# RFMxx-LPC812.net
KiCad netlist of a schematic drawn in EAGLE
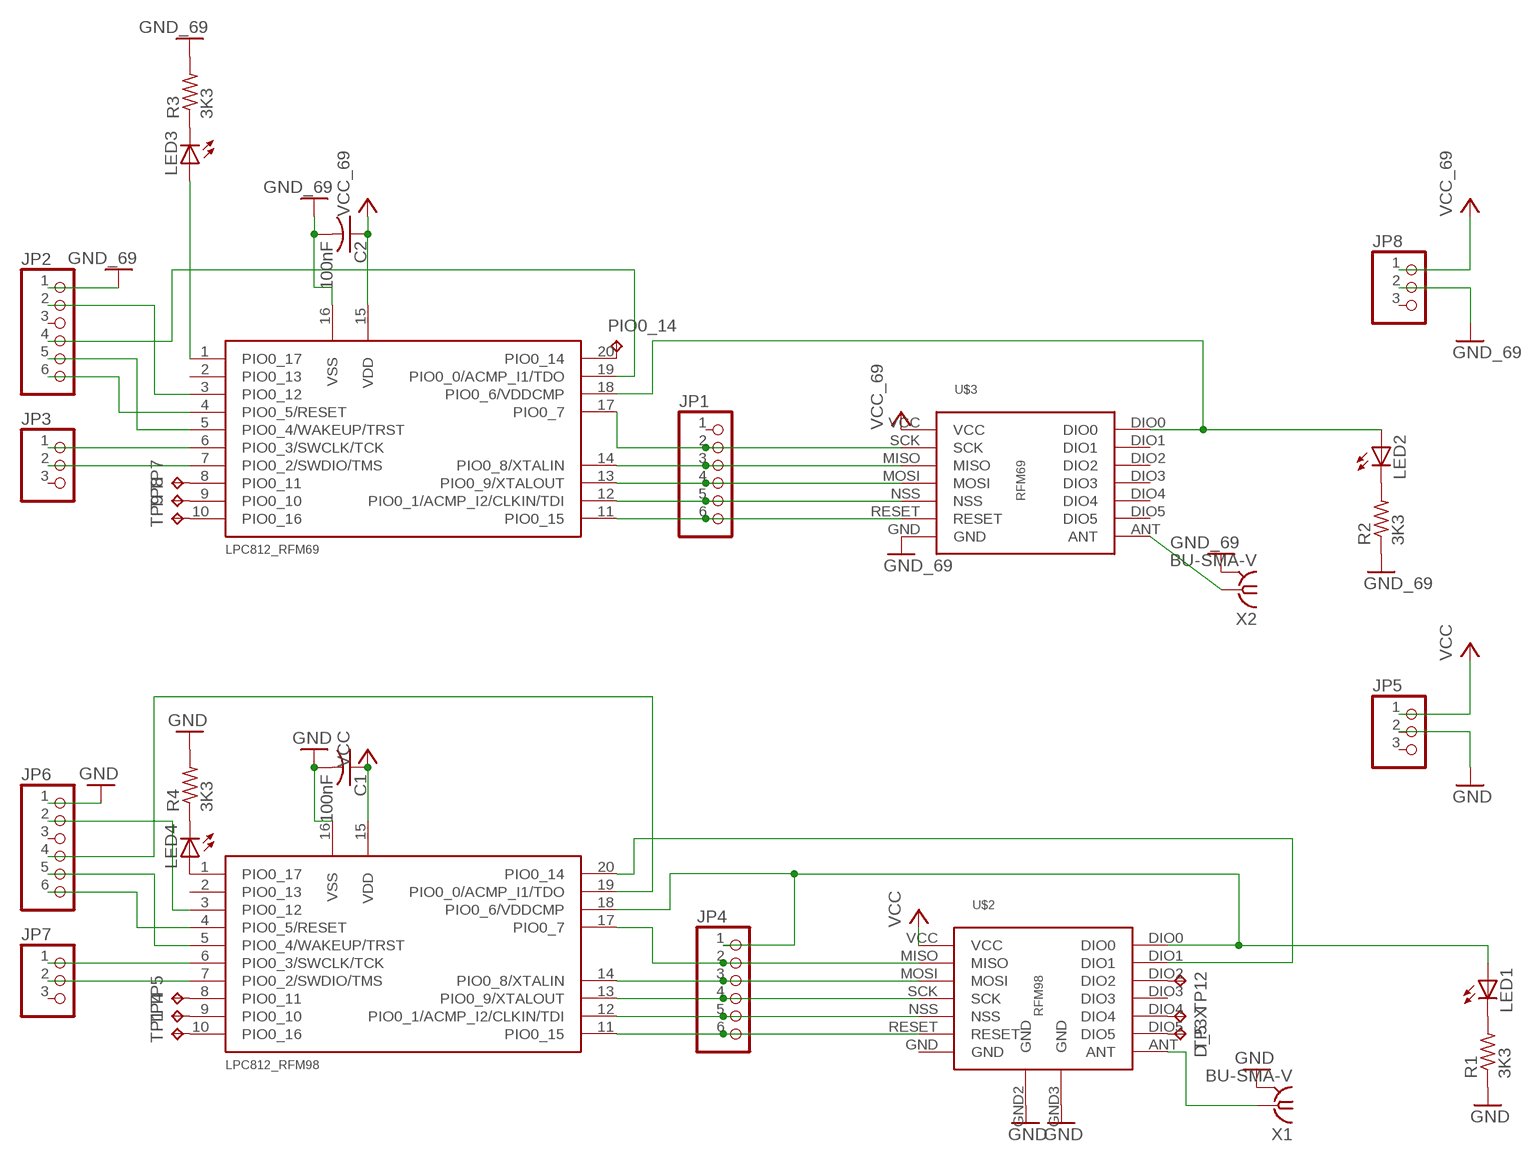
[diagram p0: schematic, sheet 1]

(export (version "E")
  (design (tool "Eeschema 10.0.6"))
  (components
    (comp (ref "C1")
      (value "100nF")
      (footprint "eagle-import:C0805")
      (libsource (lib "eagle-import") (part "C-USC0805"))
    )
    (comp (ref "C2")
      (value "100nF")
      (footprint "eagle-import:C0805")
      (libsource (lib "eagle-import") (part "C-USC0805"))
    )
    (comp (ref "D_5")
      (value "TPB1,27")
      (footprint "eagle-import:B1,27")
      (libsource (lib "eagle-import") (part "TPB1,27"))
    )
    (comp (ref "JP1")
      (value "PINHD-1X6")
      (footprint "eagle-import:1X06")
      (libsource (lib "eagle-import") (part "PINHD-1X6"))
    )
    (comp (ref "JP2")
      (value "PINHD-1X6")
      (footprint "eagle-import:1X06")
      (libsource (lib "eagle-import") (part "PINHD-1X6"))
    )
    (comp (ref "JP3")
      (value "PINHD-1X3")
      (footprint "eagle-import:1X03")
      (libsource (lib "eagle-import") (part "PINHD-1X3"))
    )
    (comp (ref "JP4")
      (value "PINHD-1X6")
      (footprint "eagle-import:1X06")
      (libsource (lib "eagle-import") (part "PINHD-1X6"))
    )
    (comp (ref "JP5")
      (value "PINHD-1X3")
      (footprint "eagle-import:1X03")
      (libsource (lib "eagle-import") (part "PINHD-1X3"))
    )
    (comp (ref "JP6")
      (value "PINHD-1X6")
      (footprint "eagle-import:1X06")
      (libsource (lib "eagle-import") (part "PINHD-1X6"))
    )
    (comp (ref "JP7")
      (value "PINHD-1X3")
      (footprint "eagle-import:1X03")
      (libsource (lib "eagle-import") (part "PINHD-1X3"))
    )
    (comp (ref "JP8")
      (value "PINHD-1X3")
      (footprint "eagle-import:1X03")
      (libsource (lib "eagle-import") (part "PINHD-1X3"))
    )
    (comp (ref "LED1")
      (value "LEDCHIP-LED0805")
      (footprint "eagle-import:CHIP-LED0805")
      (libsource (lib "eagle-import") (part "LEDCHIP-LED0805"))
    )
    (comp (ref "LED2")
      (value "LEDCHIP-LED0805")
      (footprint "eagle-import:CHIP-LED0805")
      (libsource (lib "eagle-import") (part "LEDCHIP-LED0805"))
    )
    (comp (ref "LED3")
      (value "LEDCHIP-LED0805")
      (footprint "eagle-import:CHIP-LED0805")
      (libsource (lib "eagle-import") (part "LEDCHIP-LED0805"))
    )
    (comp (ref "LED4")
      (value "LEDCHIP-LED0805")
      (footprint "eagle-import:CHIP-LED0805")
      (libsource (lib "eagle-import") (part "LEDCHIP-LED0805"))
    )
    (comp (ref "LPC812_RFM69")
      (value "LPC812M101JD20")
      (footprint "eagle-import:SOIC20")
      (libsource (lib "eagle-import") (part "LPC812M101JD20"))
    )
    (comp (ref "LPC812_RFM98")
      (value "LPC812M101JD20")
      (footprint "eagle-import:SOIC20")
      (libsource (lib "eagle-import") (part "LPC812M101JD20"))
    )
    (comp (ref "PIO0_14")
      (value "TPB1,27")
      (footprint "eagle-import:B1,27")
      (libsource (lib "eagle-import") (part "TPB1,27"))
    )
    (comp (ref "R1")
      (value "3K3")
      (footprint "eagle-import:R0805")
      (libsource (lib "eagle-import") (part "R-US_R0805"))
    )
    (comp (ref "R2")
      (value "3K3")
      (footprint "eagle-import:R0805")
      (libsource (lib "eagle-import") (part "R-US_R0805"))
    )
    (comp (ref "R3")
      (value "3K3")
      (footprint "eagle-import:R0805")
      (libsource (lib "eagle-import") (part "R-US_R0805"))
    )
    (comp (ref "R4")
      (value "3K3")
      (footprint "eagle-import:R0805")
      (libsource (lib "eagle-import") (part "R-US_R0805"))
    )
    (comp (ref "TP1")
      (value "TPB1,27")
      (footprint "eagle-import:B1,27")
      (libsource (lib "eagle-import") (part "TPB1,27"))
    )
    (comp (ref "TP3X")
      (value "TPB1,27")
      (footprint "eagle-import:B1,27")
      (libsource (lib "eagle-import") (part "TPB1,27"))
    )
    (comp (ref "TP4")
      (value "TPB1,27")
      (footprint "eagle-import:B1,27")
      (libsource (lib "eagle-import") (part "TPB1,27"))
    )
    (comp (ref "TP5")
      (value "TPB1,27")
      (footprint "eagle-import:B1,27")
      (libsource (lib "eagle-import") (part "TPB1,27"))
    )
    (comp (ref "TP7")
      (value "TPB1,27")
      (footprint "eagle-import:B1,27")
      (libsource (lib "eagle-import") (part "TPB1,27"))
    )
    (comp (ref "TP8")
      (value "TPB1,27")
      (footprint "eagle-import:B1,27")
      (libsource (lib "eagle-import") (part "TPB1,27"))
    )
    (comp (ref "TP9")
      (value "TPB1,27")
      (footprint "eagle-import:B1,27")
      (libsource (lib "eagle-import") (part "TPB1,27"))
    )
    (comp (ref "TP12")
      (value "TPB1,27")
      (footprint "eagle-import:B1,27")
      (libsource (lib "eagle-import") (part "TPB1,27"))
    )
    (comp (ref "U$2")
      (value "RFM98W")
      (footprint "eagle-import:RFM98_PADS")
      (libsource (lib "eagle-import") (part "RFM98W"))
    )
    (comp (ref "U$3")
      (value "RFM69HW")
      (footprint "eagle-import:RFM69_PADS")
      (libsource (lib "eagle-import") (part "RFM69HW"))
    )
    (comp (ref "X1")
      (value "BU-SMA-V")
      (footprint "eagle-import:BU-SMA-V")
      (libsource (lib "eagle-import") (part "BU-SMA-V"))
    )
    (comp (ref "X2")
      (value "BU-SMA-V")
      (footprint "eagle-import:BU-SMA-V")
      (libsource (lib "eagle-import") (part "BU-SMA-V"))
    )
  )
  (nets
    (net (code "1") (name "GND") (class "Default")
      (node (ref "C1") (pin "2") (pinfunction "2_2") (pintype "passive"))
      (node (ref "C2") (pin "2") (pinfunction "2_2") (pintype "passive"))
      (node (ref "JP2") (pin "1") (pinfunction "1_1") (pintype "passive"))
      (node (ref "JP5") (pin "2") (pinfunction "2_2") (pintype "passive"))
      (node (ref "JP6") (pin "1") (pinfunction "1_1") (pintype "passive"))
      (node (ref "JP8") (pin "2") (pinfunction "2_2") (pintype "passive"))
      (node (ref "LPC812_RFM69") (pin "16") (pinfunction "VSS_16") (pintype "bidirectional"))
      (node (ref "LPC812_RFM98") (pin "16") (pinfunction "VSS_16") (pintype "bidirectional"))
      (node (ref "R1") (pin "1") (pinfunction "1_1") (pintype "passive"))
      (node (ref "R2") (pin "1") (pinfunction "1_1") (pintype "passive"))
      (node (ref "R3") (pin "2") (pinfunction "2_2") (pintype "passive"))
      (node (ref "R4") (pin "2") (pinfunction "2_2") (pintype "passive"))
      (node (ref "U$2") (pin "GND2") (pinfunction "GND_GND2") (pintype "bidirectional"))
      (node (ref "U$2") (pin "GND3") (pinfunction "GND_GND3") (pintype "bidirectional"))
      (node (ref "U$3") (pin "GND") (pinfunction "GND_GND") (pintype "bidirectional"))
      (node (ref "X1") (pin "2") (pinfunction "2_2") (pintype "passive"))
      (node (ref "X1") (pin "3") (pinfunction "2_3") (pintype "passive"))
      (node (ref "X1") (pin "4") (pinfunction "2_4") (pintype "passive"))
      (node (ref "X1") (pin "5") (pinfunction "2_5") (pintype "passive"))
      (node (ref "X2") (pin "2") (pinfunction "2_2") (pintype "passive"))
      (node (ref "X2") (pin "3") (pinfunction "2_3") (pintype "passive"))
      (node (ref "X2") (pin "4") (pinfunction "2_4") (pintype "passive"))
      (node (ref "X2") (pin "5") (pinfunction "2_5") (pintype "passive"))
    )
    (net (code "2") (name "Net-(D_5-PadTP)") (class "Default")
      (node (ref "D_5") (pin "TP") (pinfunction "TP_TP") (pintype "input"))
      (node (ref "U$2") (pin "DIO5") (pinfunction "DIO5_DIO5") (pintype "bidirectional"))
    )
    (net (code "3") (name "Net-(LED1-PadC)") (class "Default")
      (node (ref "LED1") (pin "C") (pinfunction "C_C") (pintype "passive"))
      (node (ref "R1") (pin "2") (pinfunction "2_2") (pintype "passive"))
    )
    (net (code "4") (name "Net-(LED2-PadC)") (class "Default")
      (node (ref "LED2") (pin "C") (pinfunction "C_C") (pintype "passive"))
      (node (ref "R2") (pin "2") (pinfunction "2_2") (pintype "passive"))
    )
    (net (code "5") (name "Net-(LED3-PadC)") (class "Default")
      (node (ref "LED3") (pin "C") (pinfunction "C_C") (pintype "passive"))
      (node (ref "R3") (pin "1") (pinfunction "1_1") (pintype "passive"))
    )
    (net (code "6") (name "Net-(LED4-PadC)") (class "Default")
      (node (ref "LED4") (pin "C") (pinfunction "C_C") (pintype "passive"))
      (node (ref "R4") (pin "1") (pinfunction "1_1") (pintype "passive"))
    )
    (net (code "7") (name "Net-(LPC812_RFM69-PIO0_0{slash}ACMP_I1{slash}TDO)") (class "Default")
      (node (ref "JP2") (pin "4") (pinfunction "4_4") (pintype "passive"))
      (node (ref "LPC812_RFM69") (pin "19") (pinfunction "PIO0_0/ACMP_I1/TDO_19") (pintype "bidirectional"))
    )
    (net (code "8") (name "Net-(LPC812_RFM69-PIO0_1{slash}ACMP_I2{slash}CLKIN{slash}TDI)") (class "Default")
      (node (ref "JP1") (pin "5") (pinfunction "5_5") (pintype "passive"))
      (node (ref "LPC812_RFM69") (pin "12") (pinfunction "PIO0_1/ACMP_I2/CLKIN/TDI_12") (pintype "bidirectional"))
      (node (ref "U$3") (pin "NSS") (pinfunction "NSS_NSS") (pintype "bidirectional"))
    )
    (net (code "9") (name "Net-(LPC812_RFM69-PIO0_2{slash}SWDIO{slash}TMS)") (class "Default")
      (node (ref "JP3") (pin "2") (pinfunction "2_2") (pintype "passive"))
      (node (ref "LPC812_RFM69") (pin "7") (pinfunction "PIO0_2/SWDIO/TMS_7") (pintype "bidirectional"))
    )
    (net (code "10") (name "Net-(LPC812_RFM69-PIO0_3{slash}SWCLK{slash}TCK)") (class "Default")
      (node (ref "JP3") (pin "1") (pinfunction "1_1") (pintype "passive"))
      (node (ref "LPC812_RFM69") (pin "6") (pinfunction "PIO0_3/SWCLK/TCK_6") (pintype "bidirectional"))
    )
    (net (code "11") (name "Net-(LPC812_RFM69-PIO0_4{slash}WAKEUP{slash}TRST)") (class "Default")
      (node (ref "JP2") (pin "5") (pinfunction "5_5") (pintype "passive"))
      (node (ref "LPC812_RFM69") (pin "5") (pinfunction "PIO0_4/WAKEUP/TRST_5") (pintype "bidirectional"))
    )
    (net (code "12") (name "Net-(LPC812_RFM69-PIO0_5{slash}RESET)") (class "Default")
      (node (ref "JP2") (pin "6") (pinfunction "6_6") (pintype "passive"))
      (node (ref "LPC812_RFM69") (pin "4") (pinfunction "PIO0_5/RESET_4") (pintype "bidirectional"))
    )
    (net (code "13") (name "Net-(LPC812_RFM69-PIO0_6{slash}VDDCMP)") (class "Default")
      (node (ref "LED2") (pin "A") (pinfunction "A_A") (pintype "passive"))
      (node (ref "LPC812_RFM69") (pin "18") (pinfunction "PIO0_6/VDDCMP_18") (pintype "bidirectional"))
      (node (ref "U$3") (pin "DIO0") (pinfunction "DIO0_DIO0") (pintype "bidirectional"))
    )
    (net (code "14") (name "Net-(LPC812_RFM69-PIO0_7)") (class "Default")
      (node (ref "JP1") (pin "2") (pinfunction "2_2") (pintype "passive"))
      (node (ref "LPC812_RFM69") (pin "17") (pinfunction "PIO0_7_17") (pintype "bidirectional"))
      (node (ref "U$3") (pin "SCK") (pinfunction "SCK_SCK") (pintype "bidirectional"))
    )
    (net (code "15") (name "Net-(LPC812_RFM69-PIO0_8{slash}XTALIN)") (class "Default")
      (node (ref "JP1") (pin "3") (pinfunction "3_3") (pintype "passive"))
      (node (ref "LPC812_RFM69") (pin "14") (pinfunction "PIO0_8/XTALIN_14") (pintype "bidirectional"))
      (node (ref "U$3") (pin "MISO") (pinfunction "MISO_MISO") (pintype "bidirectional"))
    )
    (net (code "16") (name "Net-(LPC812_RFM69-PIO0_9{slash}XTALOUT)") (class "Default")
      (node (ref "JP1") (pin "4") (pinfunction "4_4") (pintype "passive"))
      (node (ref "LPC812_RFM69") (pin "13") (pinfunction "PIO0_9/XTALOUT_13") (pintype "bidirectional"))
      (node (ref "U$3") (pin "MOSI") (pinfunction "MOSI_MOSI") (pintype "bidirectional"))
    )
    (net (code "17") (name "Net-(LPC812_RFM69-PIO0_10)") (class "Default")
      (node (ref "LPC812_RFM69") (pin "9") (pinfunction "PIO0_10_9") (pintype "bidirectional"))
      (node (ref "TP8") (pin "TP") (pinfunction "TP_TP") (pintype "input"))
    )
    (net (code "18") (name "Net-(LPC812_RFM69-PIO0_11)") (class "Default")
      (node (ref "LPC812_RFM69") (pin "8") (pinfunction "PIO0_11_8") (pintype "bidirectional"))
      (node (ref "TP7") (pin "TP") (pinfunction "TP_TP") (pintype "input"))
    )
    (net (code "19") (name "Net-(LPC812_RFM69-PIO0_12)") (class "Default")
      (node (ref "JP2") (pin "2") (pinfunction "2_2") (pintype "passive"))
      (node (ref "LPC812_RFM69") (pin "3") (pinfunction "PIO0_12_3") (pintype "bidirectional"))
    )
    (net (code "20") (name "Net-(LPC812_RFM69-PIO0_14)") (class "Default")
      (node (ref "LPC812_RFM69") (pin "20") (pinfunction "PIO0_14_20") (pintype "bidirectional"))
      (node (ref "PIO0_14") (pin "TP") (pinfunction "TP_TP") (pintype "input"))
    )
    (net (code "21") (name "Net-(LPC812_RFM69-PIO0_15)") (class "Default")
      (node (ref "JP1") (pin "6") (pinfunction "6_6") (pintype "passive"))
      (node (ref "LPC812_RFM69") (pin "11") (pinfunction "PIO0_15_11") (pintype "bidirectional"))
      (node (ref "U$3") (pin "RESET") (pinfunction "RESET_RESET") (pintype "bidirectional"))
    )
    (net (code "22") (name "Net-(LPC812_RFM69-PIO0_16)") (class "Default")
      (node (ref "LPC812_RFM69") (pin "10") (pinfunction "PIO0_16_10") (pintype "bidirectional"))
      (node (ref "TP9") (pin "TP") (pinfunction "TP_TP") (pintype "input"))
    )
    (net (code "23") (name "Net-(LPC812_RFM69-PIO0_17)") (class "Default")
      (node (ref "LED3") (pin "A") (pinfunction "A_A") (pintype "passive"))
      (node (ref "LPC812_RFM69") (pin "1") (pinfunction "PIO0_17_1") (pintype "bidirectional"))
    )
    (net (code "24") (name "Net-(LPC812_RFM98-PIO0_0{slash}ACMP_I1{slash}TDO)") (class "Default")
      (node (ref "JP6") (pin "4") (pinfunction "4_4") (pintype "passive"))
      (node (ref "LPC812_RFM98") (pin "19") (pinfunction "PIO0_0/ACMP_I1/TDO_19") (pintype "bidirectional"))
    )
    (net (code "25") (name "Net-(LPC812_RFM98-PIO0_1{slash}ACMP_I2{slash}CLKIN{slash}TDI)") (class "Default")
      (node (ref "JP4") (pin "5") (pinfunction "5_5") (pintype "passive"))
      (node (ref "LPC812_RFM98") (pin "12") (pinfunction "PIO0_1/ACMP_I2/CLKIN/TDI_12") (pintype "bidirectional"))
      (node (ref "U$2") (pin "NSS") (pinfunction "NSS_NSS") (pintype "bidirectional"))
    )
    (net (code "26") (name "Net-(LPC812_RFM98-PIO0_2{slash}SWDIO{slash}TMS)") (class "Default")
      (node (ref "JP7") (pin "2") (pinfunction "2_2") (pintype "passive"))
      (node (ref "LPC812_RFM98") (pin "7") (pinfunction "PIO0_2/SWDIO/TMS_7") (pintype "bidirectional"))
    )
    (net (code "27") (name "Net-(LPC812_RFM98-PIO0_3{slash}SWCLK{slash}TCK)") (class "Default")
      (node (ref "JP7") (pin "1") (pinfunction "1_1") (pintype "passive"))
      (node (ref "LPC812_RFM98") (pin "6") (pinfunction "PIO0_3/SWCLK/TCK_6") (pintype "bidirectional"))
    )
    (net (code "28") (name "Net-(LPC812_RFM98-PIO0_4{slash}WAKEUP{slash}TRST)") (class "Default")
      (node (ref "JP6") (pin "5") (pinfunction "5_5") (pintype "passive"))
      (node (ref "LPC812_RFM98") (pin "5") (pinfunction "PIO0_4/WAKEUP/TRST_5") (pintype "bidirectional"))
    )
    (net (code "29") (name "Net-(LPC812_RFM98-PIO0_5{slash}RESET)") (class "Default")
      (node (ref "JP6") (pin "6") (pinfunction "6_6") (pintype "passive"))
      (node (ref "LPC812_RFM98") (pin "4") (pinfunction "PIO0_5/RESET_4") (pintype "bidirectional"))
    )
    (net (code "30") (name "Net-(LPC812_RFM98-PIO0_6{slash}VDDCMP)") (class "Default")
      (node (ref "JP4") (pin "1") (pinfunction "1_1") (pintype "passive"))
      (node (ref "LED1") (pin "A") (pinfunction "A_A") (pintype "passive"))
      (node (ref "LPC812_RFM98") (pin "18") (pinfunction "PIO0_6/VDDCMP_18") (pintype "bidirectional"))
      (node (ref "U$2") (pin "DIO0") (pinfunction "DIO0_DIO0") (pintype "bidirectional"))
    )
    (net (code "31") (name "Net-(LPC812_RFM98-PIO0_7)") (class "Default")
      (node (ref "JP4") (pin "2") (pinfunction "2_2") (pintype "passive"))
      (node (ref "LPC812_RFM98") (pin "17") (pinfunction "PIO0_7_17") (pintype "bidirectional"))
      (node (ref "U$2") (pin "MISO") (pinfunction "MISO_MISO") (pintype "bidirectional"))
    )
    (net (code "32") (name "Net-(LPC812_RFM98-PIO0_8{slash}XTALIN)") (class "Default")
      (node (ref "JP4") (pin "3") (pinfunction "3_3") (pintype "passive"))
      (node (ref "LPC812_RFM98") (pin "14") (pinfunction "PIO0_8/XTALIN_14") (pintype "bidirectional"))
      (node (ref "U$2") (pin "MOSI") (pinfunction "MOSI_MOSI") (pintype "bidirectional"))
    )
    (net (code "33") (name "Net-(LPC812_RFM98-PIO0_9{slash}XTALOUT)") (class "Default")
      (node (ref "JP4") (pin "4") (pinfunction "4_4") (pintype "passive"))
      (node (ref "LPC812_RFM98") (pin "13") (pinfunction "PIO0_9/XTALOUT_13") (pintype "bidirectional"))
      (node (ref "U$2") (pin "SCK") (pinfunction "SCK_SCK") (pintype "bidirectional"))
    )
    (net (code "34") (name "Net-(LPC812_RFM98-PIO0_10)") (class "Default")
      (node (ref "LPC812_RFM98") (pin "9") (pinfunction "PIO0_10_9") (pintype "bidirectional"))
      (node (ref "TP4") (pin "TP") (pinfunction "TP_TP") (pintype "input"))
    )
    (net (code "35") (name "Net-(LPC812_RFM98-PIO0_11)") (class "Default")
      (node (ref "LPC812_RFM98") (pin "8") (pinfunction "PIO0_11_8") (pintype "bidirectional"))
      (node (ref "TP5") (pin "TP") (pinfunction "TP_TP") (pintype "input"))
    )
    (net (code "36") (name "Net-(LPC812_RFM98-PIO0_12)") (class "Default")
      (node (ref "JP6") (pin "2") (pinfunction "2_2") (pintype "passive"))
      (node (ref "LPC812_RFM98") (pin "3") (pinfunction "PIO0_12_3") (pintype "bidirectional"))
    )
    (net (code "37") (name "Net-(LPC812_RFM98-PIO0_14)") (class "Default")
      (node (ref "LPC812_RFM98") (pin "20") (pinfunction "PIO0_14_20") (pintype "bidirectional"))
      (node (ref "U$2") (pin "DIO1") (pinfunction "DIO1_DIO1") (pintype "bidirectional"))
    )
    (net (code "38") (name "Net-(LPC812_RFM98-PIO0_15)") (class "Default")
      (node (ref "JP4") (pin "6") (pinfunction "6_6") (pintype "passive"))
      (node (ref "LPC812_RFM98") (pin "11") (pinfunction "PIO0_15_11") (pintype "bidirectional"))
      (node (ref "U$2") (pin "RESET") (pinfunction "RESET_RESET") (pintype "bidirectional"))
    )
    (net (code "39") (name "Net-(LPC812_RFM98-PIO0_16)") (class "Default")
      (node (ref "LPC812_RFM98") (pin "10") (pinfunction "PIO0_16_10") (pintype "bidirectional"))
      (node (ref "TP1") (pin "TP") (pinfunction "TP_TP") (pintype "input"))
    )
    (net (code "40") (name "Net-(LPC812_RFM98-PIO0_17)") (class "Default")
      (node (ref "LED4") (pin "A") (pinfunction "A_A") (pintype "passive"))
      (node (ref "LPC812_RFM98") (pin "1") (pinfunction "PIO0_17_1") (pintype "bidirectional"))
    )
    (net (code "41") (name "Net-(TP3X-PadTP)") (class "Default")
      (node (ref "TP3X") (pin "TP") (pinfunction "TP_TP") (pintype "input"))
      (node (ref "U$2") (pin "DIO4") (pinfunction "DIO4_DIO4") (pintype "bidirectional"))
    )
    (net (code "42") (name "Net-(TP12-PadTP)") (class "Default")
      (node (ref "TP12") (pin "TP") (pinfunction "TP_TP") (pintype "input"))
      (node (ref "U$2") (pin "DIO2") (pinfunction "DIO2_DIO2") (pintype "bidirectional"))
    )
    (net (code "43") (name "Net-(U$2-PadANT)") (class "Default")
      (node (ref "U$2") (pin "ANT") (pinfunction "ANT_ANT") (pintype "bidirectional"))
      (node (ref "X1") (pin "1") (pinfunction "1_1") (pintype "passive"))
    )
    (net (code "44") (name "Net-(U$3-PadANT)") (class "Default")
      (node (ref "U$3") (pin "ANT") (pinfunction "ANT_ANT") (pintype "bidirectional"))
      (node (ref "X2") (pin "1") (pinfunction "1_1") (pintype "passive"))
    )
    (net (code "45") (name "VCC") (class "Default")
      (node (ref "C1") (pin "1") (pinfunction "1_1") (pintype "passive"))
      (node (ref "C2") (pin "1") (pinfunction "1_1") (pintype "passive"))
      (node (ref "JP5") (pin "1") (pinfunction "1_1") (pintype "passive"))
      (node (ref "JP8") (pin "1") (pinfunction "1_1") (pintype "passive"))
      (node (ref "LPC812_RFM69") (pin "15") (pinfunction "VDD_15") (pintype "bidirectional"))
      (node (ref "LPC812_RFM98") (pin "15") (pinfunction "VDD_15") (pintype "bidirectional"))
      (node (ref "U$2") (pin "VCC") (pinfunction "VCC_VCC") (pintype "bidirectional"))
      (node (ref "U$3") (pin "VCC") (pinfunction "VCC_VCC") (pintype "bidirectional"))
    )
    (net (code "46") (name "unconnected-(JP1-Pad1)") (class "Default")
      (node (ref "JP1") (pin "1") (pinfunction "1_1") (pintype "passive"))
    )
    (net (code "47") (name "unconnected-(JP2-Pad3)") (class "Default")
      (node (ref "JP2") (pin "3") (pinfunction "3_3") (pintype "passive"))
    )
    (net (code "48") (name "unconnected-(JP3-Pad3)") (class "Default")
      (node (ref "JP3") (pin "3") (pinfunction "3_3") (pintype "passive"))
    )
    (net (code "49") (name "unconnected-(JP5-Pad3)") (class "Default")
      (node (ref "JP5") (pin "3") (pinfunction "3_3") (pintype "passive"))
    )
    (net (code "50") (name "unconnected-(JP6-Pad3)") (class "Default")
      (node (ref "JP6") (pin "3") (pinfunction "3_3") (pintype "passive"))
    )
    (net (code "51") (name "unconnected-(JP7-Pad3)") (class "Default")
      (node (ref "JP7") (pin "3") (pinfunction "3_3") (pintype "passive"))
    )
    (net (code "52") (name "unconnected-(JP8-Pad3)") (class "Default")
      (node (ref "JP8") (pin "3") (pinfunction "3_3") (pintype "passive"))
    )
    (net (code "53") (name "unconnected-(LPC812_RFM69-PIO0_13-Pad2)") (class "Default")
      (node (ref "LPC812_RFM69") (pin "2") (pinfunction "PIO0_13_2") (pintype "bidirectional"))
    )
    (net (code "54") (name "unconnected-(LPC812_RFM98-PIO0_13-Pad2)") (class "Default")
      (node (ref "LPC812_RFM98") (pin "2") (pinfunction "PIO0_13_2") (pintype "bidirectional"))
    )
    (net (code "55") (name "unconnected-(U$2-PadDIO3)") (class "Default")
      (node (ref "U$2") (pin "DIO3") (pinfunction "DIO3_DIO3") (pintype "bidirectional"))
    )
    (net (code "56") (name "unconnected-(U$2-PadGND)") (class "Default")
      (node (ref "U$2") (pin "GND") (pinfunction "GND_GND") (pintype "bidirectional"))
    )
    (net (code "57") (name "unconnected-(U$3-PadDIO1)") (class "Default")
      (node (ref "U$3") (pin "DIO1") (pinfunction "DIO1_DIO1") (pintype "bidirectional"))
    )
    (net (code "58") (name "unconnected-(U$3-PadDIO2)") (class "Default")
      (node (ref "U$3") (pin "DIO2") (pinfunction "DIO2_DIO2") (pintype "bidirectional"))
    )
    (net (code "59") (name "unconnected-(U$3-PadDIO3)") (class "Default")
      (node (ref "U$3") (pin "DIO3") (pinfunction "DIO3_DIO3") (pintype "bidirectional"))
    )
    (net (code "60") (name "unconnected-(U$3-PadDIO4)") (class "Default")
      (node (ref "U$3") (pin "DIO4") (pinfunction "DIO4_DIO4") (pintype "bidirectional"))
    )
    (net (code "61") (name "unconnected-(U$3-PadDIO5)") (class "Default")
      (node (ref "U$3") (pin "DIO5") (pinfunction "DIO5_DIO5") (pintype "bidirectional"))
    )
  )
)
